# main.net
KiCad netlist of a schematic drawn in EAGLE
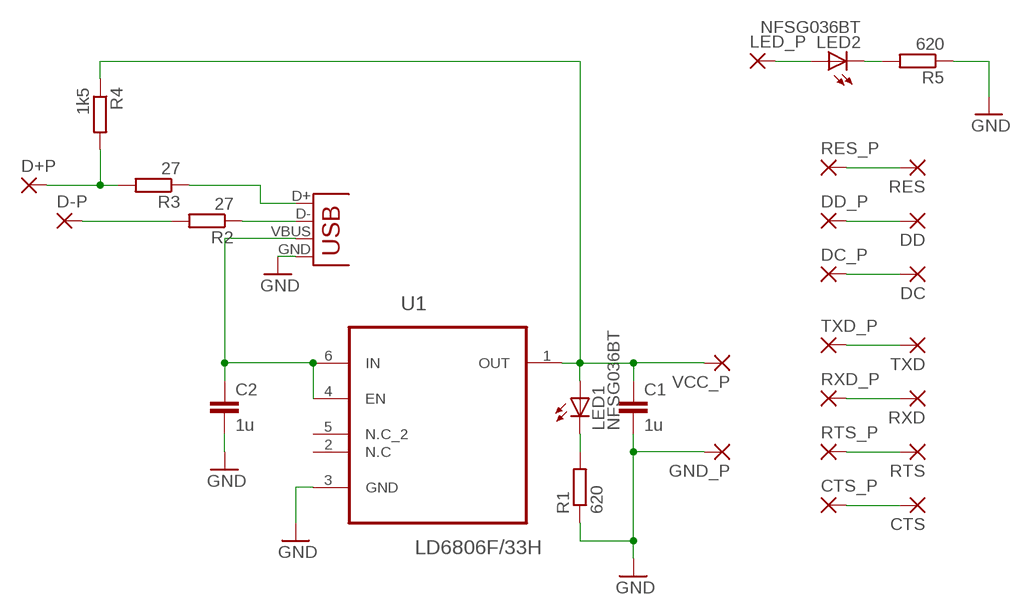
[diagram p0: schematic, sheet 1]

(export (version "E")
  (design (tool "Eeschema 10.0.6"))
  (components
    (comp (ref "C1")
      (value "1u")
      (footprint "eagle-import:C0805")
      (libsource (lib "eagle-import") (part "C-EUC0805"))
    )
    (comp (ref "C2")
      (value "1u")
      (footprint "eagle-import:C0805")
      (libsource (lib "eagle-import") (part "C-EUC0805"))
    )
    (comp (ref "CTS")
      (value "WIREPAD1,6/0,8")
      (footprint "eagle-import:1,6_0,8")
      (libsource (lib "eagle-import") (part "WIREPAD1,6/0,8"))
    )
    (comp (ref "CTS_P")
      (value "WIREPAD1,6/0,8")
      (footprint "eagle-import:1,6_0,8")
      (libsource (lib "eagle-import") (part "WIREPAD1,6/0,8"))
    )
    (comp (ref "D+P")
      (value "WIREPAD1,6/0,8")
      (footprint "eagle-import:1,6_0,8")
      (libsource (lib "eagle-import") (part "WIREPAD1,6/0,8"))
    )
    (comp (ref "D-P")
      (value "WIREPAD1,6/0,8")
      (footprint "eagle-import:1,6_0,8")
      (libsource (lib "eagle-import") (part "WIREPAD1,6/0,8"))
    )
    (comp (ref "DC")
      (value "WIREPAD1,6/0,8")
      (footprint "eagle-import:1,6_0,8")
      (libsource (lib "eagle-import") (part "WIREPAD1,6/0,8"))
    )
    (comp (ref "DC_P")
      (value "WIREPAD1,6/0,8")
      (footprint "eagle-import:1,6_0,8")
      (libsource (lib "eagle-import") (part "WIREPAD1,6/0,8"))
    )
    (comp (ref "DD")
      (value "WIREPAD1,6/0,8")
      (footprint "eagle-import:1,6_0,8")
      (libsource (lib "eagle-import") (part "WIREPAD1,6/0,8"))
    )
    (comp (ref "DD_P")
      (value "WIREPAD1,6/0,8")
      (footprint "eagle-import:1,6_0,8")
      (libsource (lib "eagle-import") (part "WIREPAD1,6/0,8"))
    )
    (comp (ref "GND_P")
      (value "WIREPAD1,6/0,8")
      (footprint "eagle-import:1,6_0,8")
      (libsource (lib "eagle-import") (part "WIREPAD1,6/0,8"))
    )
    (comp (ref "LED1")
      (value "NFSG036BT")
      (footprint "eagle-import:NFSG036BT")
      (libsource (lib "eagle-import") (part "NFSG036BT"))
    )
    (comp (ref "LED2")
      (value "NFSG036BT")
      (footprint "eagle-import:NFSG036BT")
      (libsource (lib "eagle-import") (part "NFSG036BT"))
    )
    (comp (ref "LED_P")
      (value "WIREPAD1,6/0,8")
      (footprint "eagle-import:1,6_0,8")
      (libsource (lib "eagle-import") (part "WIREPAD1,6/0,8"))
    )
    (comp (ref "R1")
      (value "620")
      (footprint "eagle-import:R0805")
      (libsource (lib "eagle-import") (part "R-EU_R0805"))
    )
    (comp (ref "R2")
      (value "27")
      (footprint "eagle-import:R0805")
      (libsource (lib "eagle-import") (part "R-EU_R0805"))
    )
    (comp (ref "R3")
      (value "27")
      (footprint "eagle-import:R0805")
      (libsource (lib "eagle-import") (part "R-EU_R0805"))
    )
    (comp (ref "R4")
      (value "1k5")
      (footprint "eagle-import:R0805")
      (libsource (lib "eagle-import") (part "R-EU_R0805"))
    )
    (comp (ref "R5")
      (value "620")
      (footprint "eagle-import:R0805")
      (libsource (lib "eagle-import") (part "R-EU_R0805"))
    )
    (comp (ref "RES")
      (value "WIREPAD1,6/0,8")
      (footprint "eagle-import:1,6_0,8")
      (libsource (lib "eagle-import") (part "WIREPAD1,6/0,8"))
    )
    (comp (ref "RES_P")
      (value "WIREPAD1,6/0,8")
      (footprint "eagle-import:1,6_0,8")
      (libsource (lib "eagle-import") (part "WIREPAD1,6/0,8"))
    )
    (comp (ref "RTS")
      (value "WIREPAD1,6/0,8")
      (footprint "eagle-import:1,6_0,8")
      (libsource (lib "eagle-import") (part "WIREPAD1,6/0,8"))
    )
    (comp (ref "RTS_P")
      (value "WIREPAD1,6/0,8")
      (footprint "eagle-import:1,6_0,8")
      (libsource (lib "eagle-import") (part "WIREPAD1,6/0,8"))
    )
    (comp (ref "RXD")
      (value "WIREPAD1,6/0,8")
      (footprint "eagle-import:1,6_0,8")
      (libsource (lib "eagle-import") (part "WIREPAD1,6/0,8"))
    )
    (comp (ref "RXD_P")
      (value "WIREPAD1,6/0,8")
      (footprint "eagle-import:1,6_0,8")
      (libsource (lib "eagle-import") (part "WIREPAD1,6/0,8"))
    )
    (comp (ref "TXD")
      (value "WIREPAD1,6/0,8")
      (footprint "eagle-import:1,6_0,8")
      (libsource (lib "eagle-import") (part "WIREPAD1,6/0,8"))
    )
    (comp (ref "TXD_P")
      (value "WIREPAD1,6/0,8")
      (footprint "eagle-import:1,6_0,8")
      (libsource (lib "eagle-import") (part "WIREPAD1,6/0,8"))
    )
    (comp (ref "U1")
      (value "LD6806F/33H")
      (footprint "eagle-import:SON50P100X145X50-6N")
      (libsource (lib "eagle-import") (part "LD6806F/33H"))
    )
    (comp (ref "VCC_P")
      (value "WIREPAD1,6/0,8")
      (footprint "eagle-import:1,6_0,8")
      (libsource (lib "eagle-import") (part "WIREPAD1,6/0,8"))
    )
    (comp (ref "X1")
      (value "USB-MICROB")
      (footprint "eagle-import:USB-MICROB")
      (libsource (lib "eagle-import") (part "USB-MICROB"))
    )
  )
  (nets
    (net (code "1") (name "GND") (class "Default")
      (node (ref "C1") (pin "2") (pinfunction "2_2") (pintype "passive"))
      (node (ref "C2") (pin "2") (pinfunction "2_2") (pintype "passive"))
      (node (ref "GND_P") (pin "1") (pinfunction "P_1") (pintype "passive"))
      (node (ref "R1") (pin "1") (pinfunction "1_1") (pintype "passive"))
      (node (ref "R5") (pin "1") (pinfunction "1_1") (pintype "passive"))
      (node (ref "U1") (pin "3") (pinfunction "GND_3") (pintype "passive"))
      (node (ref "X1") (pin "GND") (pinfunction "GND_GND") (pintype "bidirectional"))
    )
    (net (code "2") (name "Net-(CTS-P)") (class "Default")
      (node (ref "CTS") (pin "1") (pinfunction "P_1") (pintype "passive"))
      (node (ref "CTS_P") (pin "1") (pinfunction "P_1") (pintype "passive"))
    )
    (net (code "3") (name "Net-(D+P-P)") (class "Default")
      (node (ref "D+P") (pin "1") (pinfunction "P_1") (pintype "passive"))
      (node (ref "R3") (pin "2") (pinfunction "2_2") (pintype "passive"))
      (node (ref "R4") (pin "2") (pinfunction "2_2") (pintype "passive"))
    )
    (net (code "4") (name "Net-(D-P-P)") (class "Default")
      (node (ref "D-P") (pin "1") (pinfunction "P_1") (pintype "passive"))
      (node (ref "R2") (pin "2") (pinfunction "2_2") (pintype "passive"))
    )
    (net (code "5") (name "Net-(DC-P)") (class "Default")
      (node (ref "DC") (pin "1") (pinfunction "P_1") (pintype "passive"))
      (node (ref "DC_P") (pin "1") (pinfunction "P_1") (pintype "passive"))
    )
    (net (code "6") (name "Net-(DD-P)") (class "Default")
      (node (ref "DD") (pin "1") (pinfunction "P_1") (pintype "passive"))
      (node (ref "DD_P") (pin "1") (pinfunction "P_1") (pintype "passive"))
    )
    (net (code "7") (name "Net-(LED1-PadC)") (class "Default")
      (node (ref "LED1") (pin "C") (pinfunction "C_C") (pintype "passive"))
      (node (ref "R1") (pin "2") (pinfunction "2_2") (pintype "passive"))
    )
    (net (code "8") (name "Net-(LED2-PadC)") (class "Default")
      (node (ref "LED2") (pin "C") (pinfunction "C_C") (pintype "passive"))
      (node (ref "R5") (pin "2") (pinfunction "2_2") (pintype "passive"))
    )
    (net (code "9") (name "Net-(LED_P-P)") (class "Default")
      (node (ref "LED2") (pin "A") (pinfunction "A_A") (pintype "passive"))
      (node (ref "LED_P") (pin "1") (pinfunction "P_1") (pintype "passive"))
    )
    (net (code "10") (name "Net-(R2-Pad1)") (class "Default")
      (node (ref "R2") (pin "1") (pinfunction "1_1") (pintype "passive"))
      (node (ref "X1") (pin "D-") (pinfunction "D-_D-") (pintype "bidirectional"))
    )
    (net (code "11") (name "Net-(R3-Pad1)") (class "Default")
      (node (ref "R3") (pin "1") (pinfunction "1_1") (pintype "passive"))
      (node (ref "X1") (pin "D+") (pinfunction "D+_D+") (pintype "bidirectional"))
    )
    (net (code "12") (name "Net-(RES-P)") (class "Default")
      (node (ref "RES") (pin "1") (pinfunction "P_1") (pintype "passive"))
      (node (ref "RES_P") (pin "1") (pinfunction "P_1") (pintype "passive"))
    )
    (net (code "13") (name "Net-(RTS-P)") (class "Default")
      (node (ref "RTS") (pin "1") (pinfunction "P_1") (pintype "passive"))
      (node (ref "RTS_P") (pin "1") (pinfunction "P_1") (pintype "passive"))
    )
    (net (code "14") (name "Net-(RXD-P)") (class "Default")
      (node (ref "RXD") (pin "1") (pinfunction "P_1") (pintype "passive"))
      (node (ref "RXD_P") (pin "1") (pinfunction "P_1") (pintype "passive"))
    )
    (net (code "15") (name "Net-(TXD-P)") (class "Default")
      (node (ref "TXD") (pin "1") (pinfunction "P_1") (pintype "passive"))
      (node (ref "TXD_P") (pin "1") (pinfunction "P_1") (pintype "passive"))
    )
    (net (code "16") (name "Net-(U1-EN)") (class "Default")
      (node (ref "C2") (pin "1") (pinfunction "1_1") (pintype "passive"))
      (node (ref "U1") (pin "4") (pinfunction "EN_4") (pintype "input"))
      (node (ref "U1") (pin "6") (pinfunction "IN_6") (pintype "input"))
      (node (ref "X1") (pin "VBUS") (pinfunction "VBUS_VBUS") (pintype "bidirectional"))
    )
    (net (code "17") (name "Net-(U1-OUT)") (class "Default")
      (node (ref "C1") (pin "1") (pinfunction "1_1") (pintype "passive"))
      (node (ref "LED1") (pin "A") (pinfunction "A_A") (pintype "passive"))
      (node (ref "R4") (pin "1") (pinfunction "1_1") (pintype "passive"))
      (node (ref "U1") (pin "1") (pinfunction "OUT_1") (pintype "output"))
      (node (ref "VCC_P") (pin "1") (pinfunction "P_1") (pintype "passive"))
    )
    (net (code "18") (name "unconnected-(U1-N.C-Pad2)") (class "Default")
      (node (ref "U1") (pin "2") (pinfunction "N.C_2") (pintype "no_connect"))
    )
    (net (code "19") (name "unconnected-(U1-N.C_2-Pad5)") (class "Default")
      (node (ref "U1") (pin "5") (pinfunction "N.C_2_5") (pintype "no_connect"))
    )
  )
)
